# Schematic.net
KiCad netlist of a schematic drawn in EAGLE
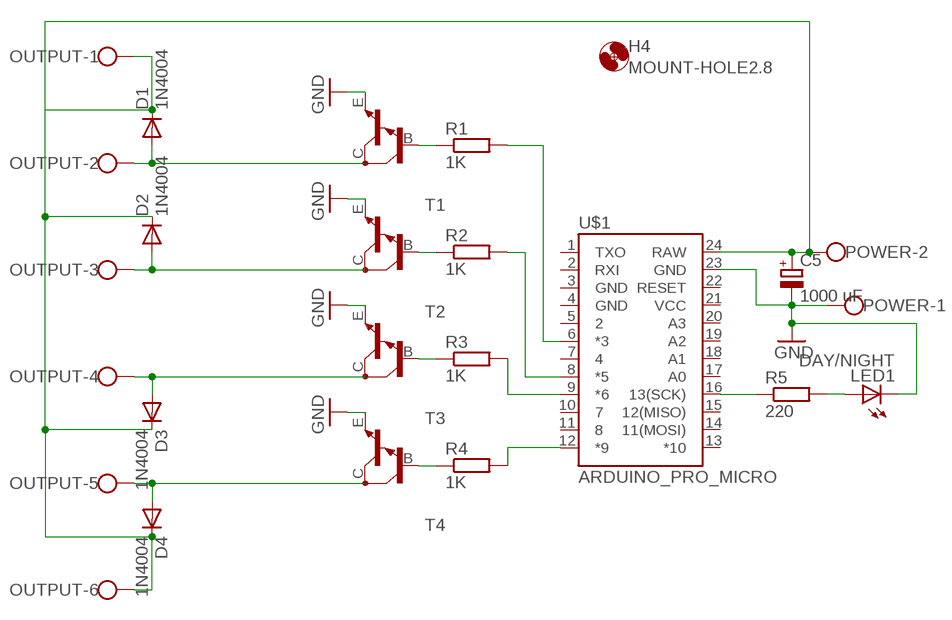
[diagram p0: schematic, sheet 1]

(export (version "E")
  (design (tool "Eeschema 10.0.6"))
  (components
    (comp (ref "C5")
      (value "1000 uF")
      (footprint "eagle-import:E5-13")
      (libsource (lib "eagle-import") (part "CPOL-EUE5-13"))
    )
    (comp (ref "D1")
      (value "1N4004")
      (footprint "eagle-import:DO41-10")
      (libsource (lib "eagle-import") (part "1N4004"))
    )
    (comp (ref "D2")
      (value "1N4004")
      (footprint "eagle-import:DO41-10")
      (libsource (lib "eagle-import") (part "1N4004"))
    )
    (comp (ref "D3")
      (value "1N4004")
      (footprint "eagle-import:DO41-10")
      (libsource (lib "eagle-import") (part "1N4004"))
    )
    (comp (ref "D4")
      (value "1N4004")
      (footprint "eagle-import:DO41-10")
      (libsource (lib "eagle-import") (part "1N4004"))
    )
    (comp (ref "H4")
      (value "MOUNT-HOLE2.8")
      (footprint "eagle-import:2,8")
      (libsource (lib "eagle-import") (part "MOUNT-HOLE2.8"))
    )
    (comp (ref "LED1")
      (value "DAY/NIGHT")
      (footprint "eagle-import:LED3MM")
      (libsource (lib "eagle-import") (part "LED3MM"))
    )
    (comp (ref "OUTPUT")
      (value "W237-136")
      (footprint "eagle-import:W237-136")
      (fields (field (name "MPN") "237-136"))
      (libsource (lib "eagle-import") (part "W237-136"))
    )
    (comp (ref "POWER")
      (value "W237-102")
      (footprint "eagle-import:W237-102")
      (fields (field (name "MPN") "237-102"))
      (libsource (lib "eagle-import") (part "W237-102"))
    )
    (comp (ref "R1")
      (value "1K")
      (footprint "eagle-import:0207_10")
      (libsource (lib "eagle-import") (part "R-EU_0207/10"))
    )
    (comp (ref "R2")
      (value "1K")
      (footprint "eagle-import:0207_10")
      (libsource (lib "eagle-import") (part "R-EU_0207/10"))
    )
    (comp (ref "R3")
      (value "1K")
      (footprint "eagle-import:0207_10")
      (libsource (lib "eagle-import") (part "R-EU_0207/10"))
    )
    (comp (ref "R4")
      (value "1K")
      (footprint "eagle-import:0207_10")
      (libsource (lib "eagle-import") (part "R-EU_0207/10"))
    )
    (comp (ref "R5")
      (value "220")
      (footprint "eagle-import:0204_7")
      (libsource (lib "eagle-import") (part "resistor_R-EU_0204/7"))
    )
    (comp (ref "T1")
      (value "TIP122VERTICAL")
      (footprint "eagle-import:TO220AV")
      (libsource (lib "eagle-import") (part "TIP122VERTICAL"))
    )
    (comp (ref "T2")
      (value "TIP122VERTICAL")
      (footprint "eagle-import:TO220AV")
      (libsource (lib "eagle-import") (part "TIP122VERTICAL"))
    )
    (comp (ref "T3")
      (value "TIP122VERTICAL")
      (footprint "eagle-import:TO220AV")
      (libsource (lib "eagle-import") (part "TIP122VERTICAL"))
    )
    (comp (ref "T4")
      (value "TIP122VERTICAL")
      (footprint "eagle-import:TO220AV")
      (libsource (lib "eagle-import") (part "TIP122VERTICAL"))
    )
    (comp (ref "U$1")
      (value "ARDUINO_PRO_MICRO")
      (footprint "eagle-import:ARDUINO_PRO_MICRO")
      (libsource (lib "eagle-import") (part "ARDUINO_PRO_MICRO"))
    )
  )
  (nets
    (net (code "1") (name "GND") (class "Default")
      (node (ref "C5") (pin "-") (pinfunction "-_-") (pintype "passive"))
      (node (ref "LED1") (pin "K") (pinfunction "C_K") (pintype "passive"))
      (node (ref "POWER") (pin "1") (pinfunction "KL_1") (pintype "passive"))
      (node (ref "T1") (pin "E") (pinfunction "E_E") (pintype "passive"))
      (node (ref "T2") (pin "E") (pinfunction "E_E") (pintype "passive"))
      (node (ref "T3") (pin "E") (pinfunction "E_E") (pintype "passive"))
      (node (ref "T4") (pin "E") (pinfunction "E_E") (pintype "passive"))
      (node (ref "U$1") (pin "23") (pinfunction "GND_23") (pintype "bidirectional"))
    )
    (net (code "2") (name "Net-(LED1-PadA)") (class "Default")
      (node (ref "LED1") (pin "A") (pinfunction "A_A") (pintype "passive"))
      (node (ref "R5") (pin "2") (pinfunction "2_2") (pintype "passive"))
    )
    (net (code "3") (name "Net-(OUTPUTA-KL)") (class "Default")
      (node (ref "C5") (pin "+") (pinfunction "+_+") (pintype "passive"))
      (node (ref "D1") (pin "C") (pinfunction "C_C") (pintype "passive"))
      (node (ref "D2") (pin "C") (pinfunction "C_C") (pintype "passive"))
      (node (ref "D3") (pin "C") (pinfunction "C_C") (pintype "passive"))
      (node (ref "D4") (pin "C") (pinfunction "C_C") (pintype "passive"))
      (node (ref "OUTPUT") (pin "1") (pinfunction "KL_1") (pintype "passive"))
      (node (ref "OUTPUT") (pin "6") (pinfunction "KL_6") (pintype "passive"))
      (node (ref "POWER") (pin "2") (pinfunction "KL_2") (pintype "passive"))
      (node (ref "U$1") (pin "24") (pinfunction "RAW_24") (pintype "bidirectional"))
    )
    (net (code "4") (name "Net-(OUTPUTB-KL)") (class "Default")
      (node (ref "D1") (pin "A") (pinfunction "A_A") (pintype "passive"))
      (node (ref "OUTPUT") (pin "2") (pinfunction "KL_2") (pintype "passive"))
      (node (ref "T1") (pin "C") (pinfunction "C_C") (pintype "passive"))
    )
    (net (code "5") (name "Net-(OUTPUTC-KL)") (class "Default")
      (node (ref "D2") (pin "A") (pinfunction "A_A") (pintype "passive"))
      (node (ref "OUTPUT") (pin "3") (pinfunction "KL_3") (pintype "passive"))
      (node (ref "T2") (pin "C") (pinfunction "C_C") (pintype "passive"))
    )
    (net (code "6") (name "Net-(OUTPUTD-KL)") (class "Default")
      (node (ref "D3") (pin "A") (pinfunction "A_A") (pintype "passive"))
      (node (ref "OUTPUT") (pin "4") (pinfunction "KL_4") (pintype "passive"))
      (node (ref "T3") (pin "C") (pinfunction "C_C") (pintype "passive"))
    )
    (net (code "7") (name "Net-(OUTPUTE-KL)") (class "Default")
      (node (ref "D4") (pin "A") (pinfunction "A_A") (pintype "passive"))
      (node (ref "OUTPUT") (pin "5") (pinfunction "KL_5") (pintype "passive"))
      (node (ref "T4") (pin "C") (pinfunction "C_C") (pintype "passive"))
    )
    (net (code "8") (name "Net-(R1-Pad1)") (class "Default")
      (node (ref "R1") (pin "1") (pinfunction "1_1") (pintype "passive"))
      (node (ref "T1") (pin "B") (pinfunction "B_B") (pintype "passive"))
    )
    (net (code "9") (name "Net-(R2-Pad1)") (class "Default")
      (node (ref "R2") (pin "1") (pinfunction "1_1") (pintype "passive"))
      (node (ref "T2") (pin "B") (pinfunction "B_B") (pintype "passive"))
    )
    (net (code "10") (name "Net-(R3-Pad1)") (class "Default")
      (node (ref "R3") (pin "1") (pinfunction "1_1") (pintype "passive"))
      (node (ref "T3") (pin "B") (pinfunction "B_B") (pintype "passive"))
    )
    (net (code "11") (name "Net-(R4-Pad1)") (class "Default")
      (node (ref "R4") (pin "1") (pinfunction "1_1") (pintype "passive"))
      (node (ref "T4") (pin "B") (pinfunction "B_B") (pintype "passive"))
    )
    (net (code "12") (name "Net-(U$1-*3)") (class "Default")
      (node (ref "R1") (pin "2") (pinfunction "2_2") (pintype "passive"))
      (node (ref "U$1") (pin "6") (pinfunction "*3_6") (pintype "bidirectional"))
    )
    (net (code "13") (name "Net-(U$1-*5)") (class "Default")
      (node (ref "R2") (pin "2") (pinfunction "2_2") (pintype "passive"))
      (node (ref "U$1") (pin "8") (pinfunction "*5_8") (pintype "bidirectional"))
    )
    (net (code "14") (name "Net-(U$1-*6)") (class "Default")
      (node (ref "R3") (pin "2") (pinfunction "2_2") (pintype "passive"))
      (node (ref "U$1") (pin "9") (pinfunction "*6_9") (pintype "bidirectional"))
    )
    (net (code "15") (name "Net-(U$1-*9)") (class "Default")
      (node (ref "R4") (pin "2") (pinfunction "2_2") (pintype "passive"))
      (node (ref "U$1") (pin "12") (pinfunction "*9_12") (pintype "bidirectional"))
    )
    (net (code "16") (name "Net-(U$1-13(SCK))") (class "Default")
      (node (ref "R5") (pin "1") (pinfunction "1_1") (pintype "passive"))
      (node (ref "U$1") (pin "16") (pinfunction "13(SCK)_16") (pintype "bidirectional"))
    )
    (net (code "17") (name "unconnected-(U$1-*10-Pad13)") (class "Default")
      (node (ref "U$1") (pin "13") (pinfunction "*10_13") (pintype "bidirectional"))
    )
    (net (code "18") (name "unconnected-(U$1-2-Pad5)") (class "Default")
      (node (ref "U$1") (pin "5") (pinfunction "2_5") (pintype "bidirectional"))
    )
    (net (code "19") (name "unconnected-(U$1-4-Pad7)") (class "Default")
      (node (ref "U$1") (pin "7") (pinfunction "4_7") (pintype "bidirectional"))
    )
    (net (code "20") (name "unconnected-(U$1-7-Pad10)") (class "Default")
      (node (ref "U$1") (pin "10") (pinfunction "7_10") (pintype "bidirectional"))
    )
    (net (code "21") (name "unconnected-(U$1-8-Pad11)") (class "Default")
      (node (ref "U$1") (pin "11") (pinfunction "8_11") (pintype "bidirectional"))
    )
    (net (code "22") (name "unconnected-(U$1-11(MOSI)-Pad14)") (class "Default")
      (node (ref "U$1") (pin "14") (pinfunction "11(MOSI)_14") (pintype "bidirectional"))
    )
    (net (code "23") (name "unconnected-(U$1-12(MISO)-Pad15)") (class "Default")
      (node (ref "U$1") (pin "15") (pinfunction "12(MISO)_15") (pintype "bidirectional"))
    )
    (net (code "24") (name "unconnected-(U$1-A0-Pad17)") (class "Default")
      (node (ref "U$1") (pin "17") (pinfunction "A0_17") (pintype "bidirectional"))
    )
    (net (code "25") (name "unconnected-(U$1-A1-Pad18)") (class "Default")
      (node (ref "U$1") (pin "18") (pinfunction "A1_18") (pintype "bidirectional"))
    )
    (net (code "26") (name "unconnected-(U$1-A2-Pad19)") (class "Default")
      (node (ref "U$1") (pin "19") (pinfunction "A2_19") (pintype "bidirectional"))
    )
    (net (code "27") (name "unconnected-(U$1-A3-Pad20)") (class "Default")
      (node (ref "U$1") (pin "20") (pinfunction "A3_20") (pintype "bidirectional"))
    )
    (net (code "28") (name "unconnected-(U$1-GND-Pad3)") (class "Default")
      (node (ref "U$1") (pin "3") (pinfunction "GND_3") (pintype "bidirectional"))
    )
    (net (code "29") (name "unconnected-(U$1-GND-Pad4)") (class "Default")
      (node (ref "U$1") (pin "4") (pinfunction "GND_4") (pintype "bidirectional"))
    )
    (net (code "30") (name "unconnected-(U$1-RESET-Pad22)") (class "Default")
      (node (ref "U$1") (pin "22") (pinfunction "RESET_22") (pintype "bidirectional"))
    )
    (net (code "31") (name "unconnected-(U$1-RXI-Pad2)") (class "Default")
      (node (ref "U$1") (pin "2") (pinfunction "RXI_2") (pintype "bidirectional"))
    )
    (net (code "32") (name "unconnected-(U$1-TXO-Pad1)") (class "Default")
      (node (ref "U$1") (pin "1") (pinfunction "TXO_1") (pintype "bidirectional"))
    )
    (net (code "33") (name "unconnected-(U$1-VCC-Pad21)") (class "Default")
      (node (ref "U$1") (pin "21") (pinfunction "VCC_21") (pintype "bidirectional"))
    )
  )
)
